# BME680.net
KiCad netlist of a schematic drawn in EAGLE
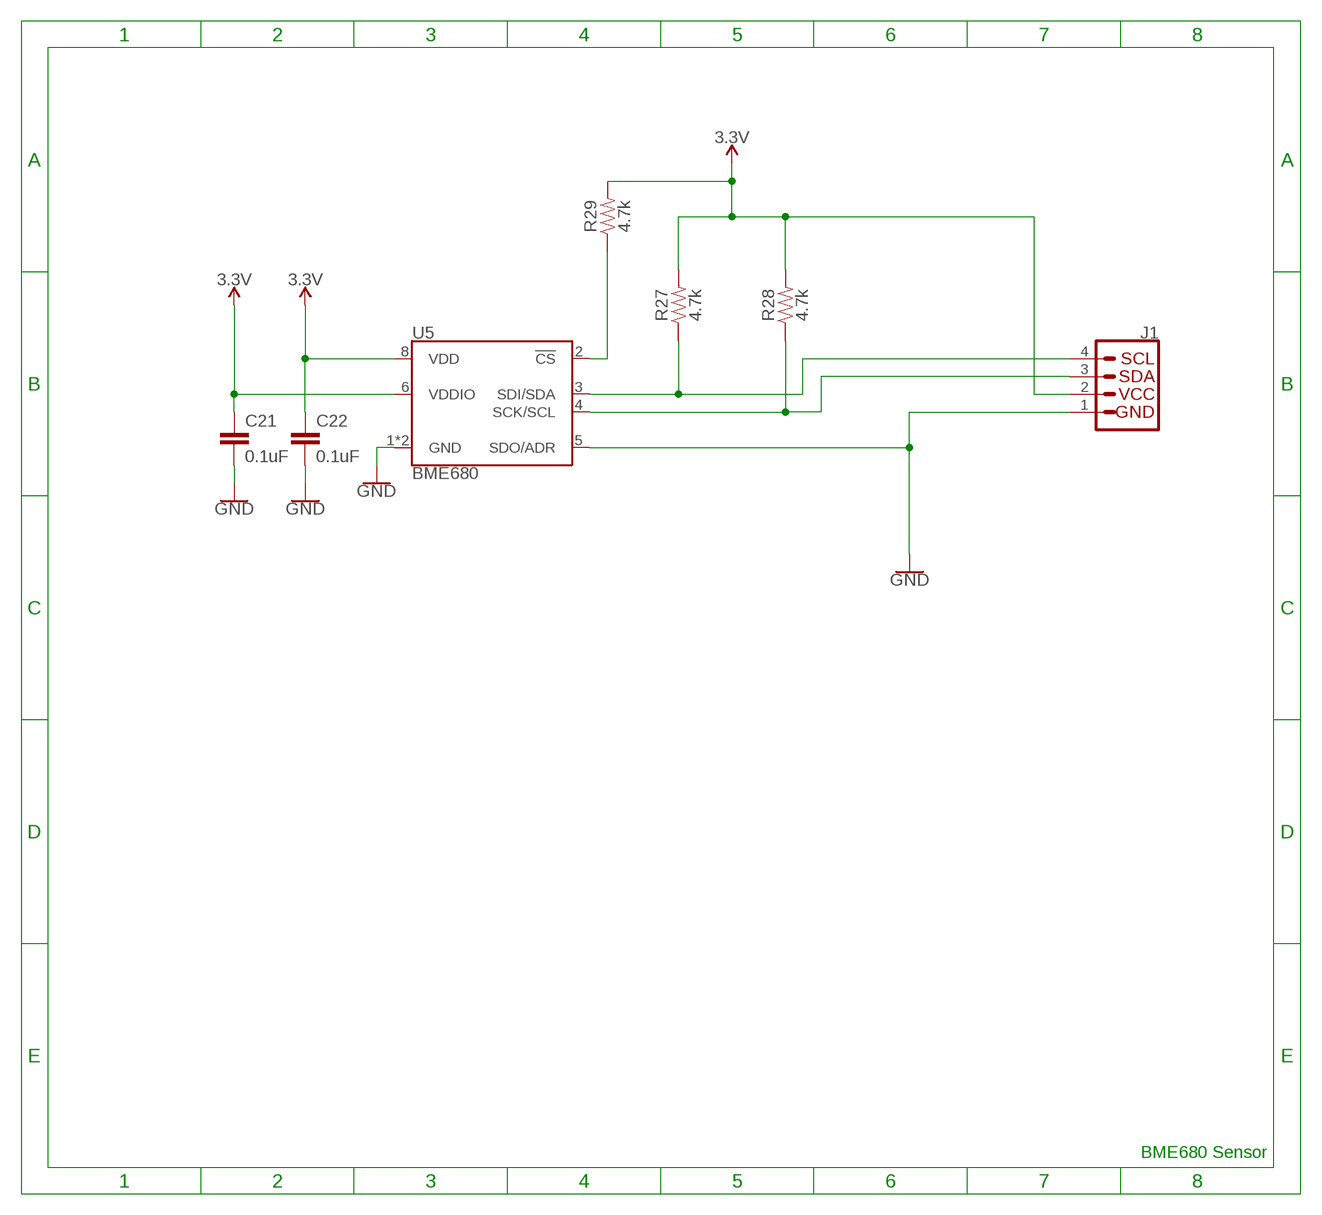
[diagram p0: schematic, sheet 1]

(export (version "E")
  (design (tool "Eeschema 10.0.6"))
  (components
    (comp (ref "C21")
      (value "0.1uF")
      (footprint "eagle-import:0603")
      (libsource (lib "eagle-import") (part "0.1UF-0603-100V-10%"))
    )
    (comp (ref "C22")
      (value "0.1uF")
      (footprint "eagle-import:0603")
      (libsource (lib "eagle-import") (part "0.1UF-0603-100V-10%"))
    )
    (comp (ref "J1")
      (value "QWIIC_CONNECTORJS-1MM")
      (footprint "eagle-import:1X04_1MM_RA@1")
      (libsource (lib "eagle-import") (part "QWIIC_CONNECTORJS-1MM"))
    )
    (comp (ref "R27")
      (value "4.7k")
      (footprint "eagle-import:0603")
      (libsource (lib "eagle-import") (part "4.7KOHM-0603-1/10W-1%"))
    )
    (comp (ref "R28")
      (value "4.7k")
      (footprint "eagle-import:0603")
      (libsource (lib "eagle-import") (part "4.7KOHM-0603-1/10W-1%"))
    )
    (comp (ref "R29")
      (value "4.7k")
      (footprint "eagle-import:0603")
      (libsource (lib "eagle-import") (part "4.7KOHM-0603-1/10W-1%"))
    )
    (comp (ref "U5")
      (value "BME680")
      (footprint "eagle-import:BME680")
      (libsource (lib "eagle-import") (part "BME680"))
    )
  )
  (nets
    (net (code "1") (name "3.3V") (class "Default")
      (node (ref "C21") (pin "1") (pinfunction "1_1") (pintype "passive"))
      (node (ref "C22") (pin "1") (pinfunction "1_1") (pintype "passive"))
      (node (ref "J1") (pin "2") (pinfunction "2_2") (pintype "power_in"))
      (node (ref "R27") (pin "2") (pinfunction "2_2") (pintype "passive"))
      (node (ref "R28") (pin "2") (pinfunction "2_2") (pintype "passive"))
      (node (ref "R29") (pin "2") (pinfunction "2_2") (pintype "passive"))
      (node (ref "U5") (pin "6") (pinfunction "VDDIO_6") (pintype "bidirectional"))
      (node (ref "U5") (pin "8") (pinfunction "VDD_8") (pintype "bidirectional"))
    )
    (net (code "2") (name "GND") (class "Default")
      (node (ref "C21") (pin "2") (pinfunction "2_2") (pintype "passive"))
      (node (ref "C22") (pin "2") (pinfunction "2_2") (pintype "passive"))
      (node (ref "J1") (pin "1") (pinfunction "1_1") (pintype "power_in"))
      (node (ref "U5") (pin "1") (pinfunction "GND_1") (pintype "bidirectional"))
      (node (ref "U5") (pin "5") (pinfunction "SDO/ADR_5") (pintype "bidirectional"))
      (node (ref "U5") (pin "7") (pinfunction "GND_7") (pintype "bidirectional"))
    )
    (net (code "3") (name "Net-(U5-SCK{slash}SCL)") (class "Default")
      (node (ref "J1") (pin "3") (pinfunction "3_3") (pintype "passive"))
      (node (ref "R28") (pin "1") (pinfunction "1_1") (pintype "passive"))
      (node (ref "U5") (pin "4") (pinfunction "SCK/SCL_4") (pintype "bidirectional"))
    )
    (net (code "4") (name "Net-(U5-SDI{slash}SDA)") (class "Default")
      (node (ref "J1") (pin "4") (pinfunction "4_4") (pintype "passive"))
      (node (ref "R27") (pin "1") (pinfunction "1_1") (pintype "passive"))
      (node (ref "U5") (pin "3") (pinfunction "SDI/SDA_3") (pintype "bidirectional"))
    )
    (net (code "5") (name "Net-(U5-~{CS})") (class "Default")
      (node (ref "R29") (pin "1") (pinfunction "1_1") (pintype "passive"))
      (node (ref "U5") (pin "2") (pinfunction "~{CS}_2") (pintype "bidirectional"))
    )
  )
)
